# Lower_Board.net
KiCad netlist of a schematic drawn in EAGLE
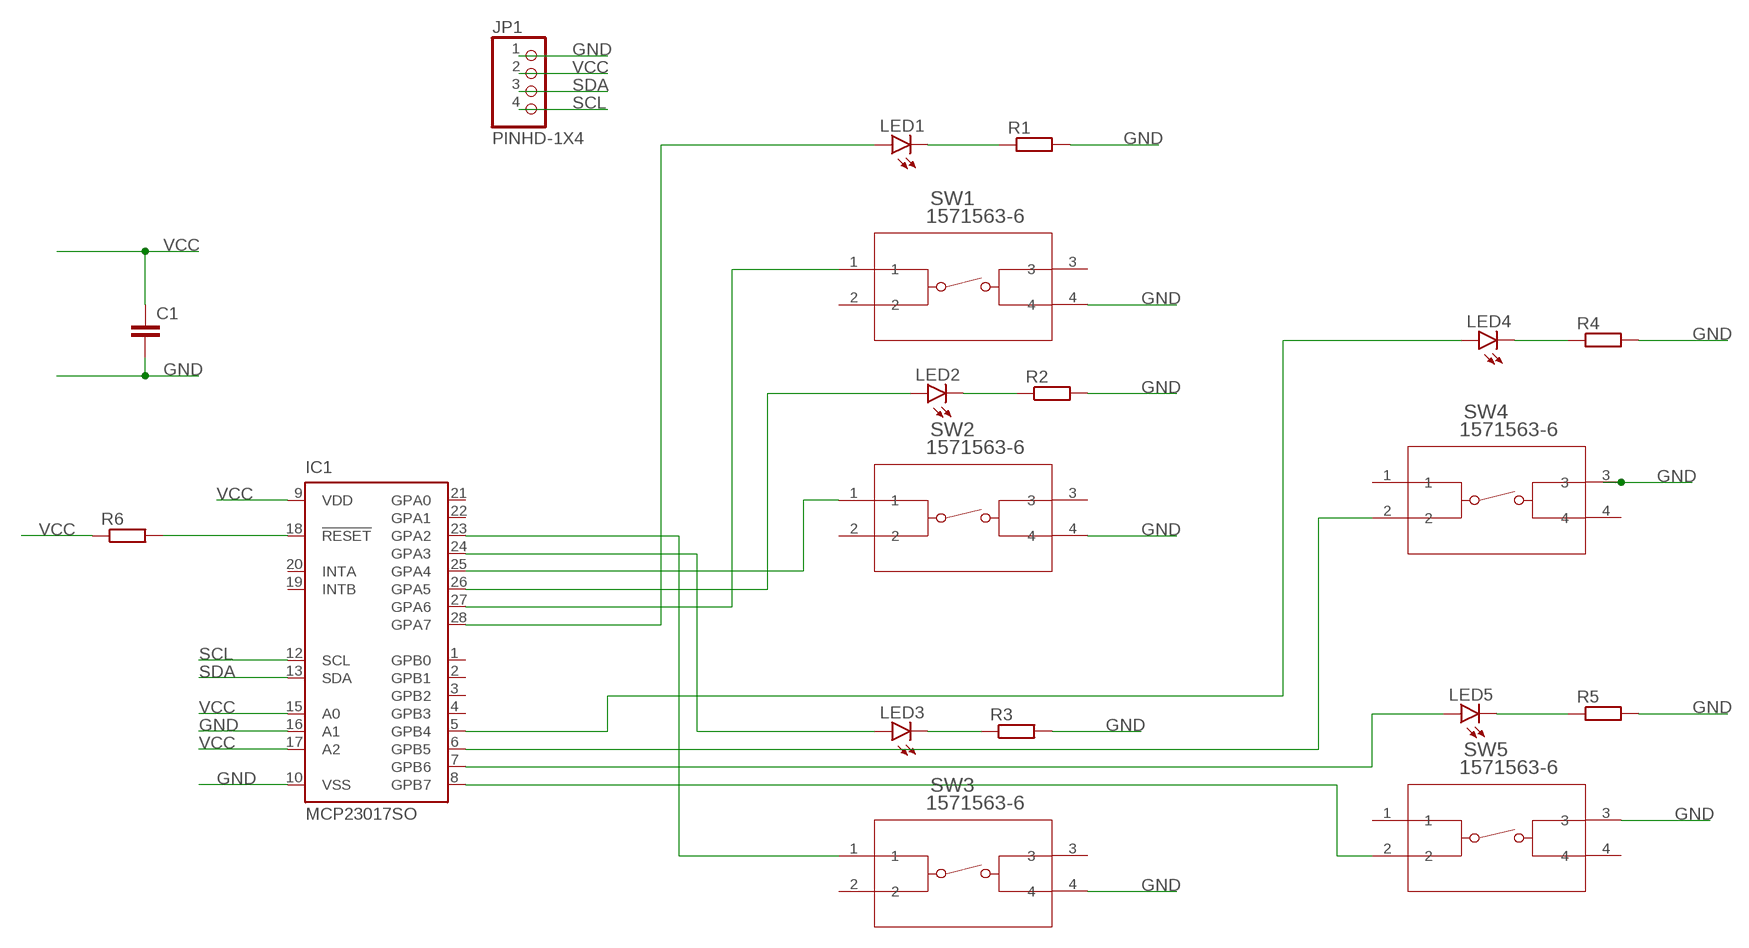
[diagram p0: schematic, sheet 1]

(export (version "E")
  (design (tool "Eeschema 10.0.6"))
  (components
    (comp (ref "C1")
      (value "C-EU025-025X050")
      (footprint "eagle-import:C025-025X050")
      (libsource (lib "eagle-import") (part "C-EU025-025X050"))
    )
    (comp (ref "IC1")
      (value "MCP23017SO")
      (footprint "eagle-import:SO28W")
      (fields (field (name "MF") "MICROCHIP") (field (name "MPN") "MCP23017-E/SO"))
      (libsource (lib "eagle-import") (part "MCP23017SO"))
    )
    (comp (ref "JP1")
      (value "PINHD-1X4")
      (footprint "eagle-import:1X04")
      (libsource (lib "eagle-import") (part "PINHD-1X4"))
    )
    (comp (ref "LED1")
      (value "LEDCHIP-LED0805")
      (footprint "eagle-import:CHIP-LED0805")
      (libsource (lib "eagle-import") (part "LEDCHIP-LED0805"))
    )
    (comp (ref "LED2")
      (value "LEDCHIP-LED0805")
      (footprint "eagle-import:CHIP-LED0805")
      (libsource (lib "eagle-import") (part "LEDCHIP-LED0805"))
    )
    (comp (ref "LED3")
      (value "LEDCHIP-LED0805")
      (footprint "eagle-import:CHIP-LED0805")
      (libsource (lib "eagle-import") (part "LEDCHIP-LED0805"))
    )
    (comp (ref "LED4")
      (value "LEDCHIP-LED0805")
      (footprint "eagle-import:CHIP-LED0805")
      (libsource (lib "eagle-import") (part "LEDCHIP-LED0805"))
    )
    (comp (ref "LED5")
      (value "LEDCHIP-LED0805")
      (footprint "eagle-import:CHIP-LED0805")
      (libsource (lib "eagle-import") (part "LEDCHIP-LED0805"))
    )
    (comp (ref "R1")
      (value "R-EU_R0805")
      (footprint "eagle-import:R0805")
      (libsource (lib "eagle-import") (part "R-EU_R0805"))
    )
    (comp (ref "R2")
      (value "R-EU_R0805")
      (footprint "eagle-import:R0805")
      (libsource (lib "eagle-import") (part "R-EU_R0805"))
    )
    (comp (ref "R3")
      (value "R-EU_R0805")
      (footprint "eagle-import:R0805")
      (libsource (lib "eagle-import") (part "R-EU_R0805"))
    )
    (comp (ref "R4")
      (value "R-EU_R0805")
      (footprint "eagle-import:R0805")
      (libsource (lib "eagle-import") (part "R-EU_R0805"))
    )
    (comp (ref "R5")
      (value "R-EU_R0805")
      (footprint "eagle-import:R0805")
      (libsource (lib "eagle-import") (part "R-EU_R0805"))
    )
    (comp (ref "R6")
      (value "R-EU_R0805")
      (footprint "eagle-import:R0805")
      (libsource (lib "eagle-import") (part "R-EU_R0805"))
    )
    (comp (ref "SW1")
      (value "1571563-6")
      (footprint "eagle-import:SW4_1437565-E")
      (fields (field (name "COPYRIGHT") "Copyright (C) 2016 Accelerated Designs. All rights reserved"))
      (libsource (lib "eagle-import") (part "1571563-6"))
    )
    (comp (ref "SW2")
      (value "1571563-6")
      (footprint "eagle-import:SW4_1437565-E")
      (fields (field (name "COPYRIGHT") "Copyright (C) 2016 Accelerated Designs. All rights reserved"))
      (libsource (lib "eagle-import") (part "1571563-6"))
    )
    (comp (ref "SW3")
      (value "1571563-6")
      (footprint "eagle-import:SW4_1437565-E")
      (fields (field (name "COPYRIGHT") "Copyright (C) 2016 Accelerated Designs. All rights reserved"))
      (libsource (lib "eagle-import") (part "1571563-6"))
    )
    (comp (ref "SW4")
      (value "1571563-6")
      (footprint "eagle-import:SW4_1437565-E")
      (fields (field (name "COPYRIGHT") "Copyright (C) 2016 Accelerated Designs. All rights reserved"))
      (libsource (lib "eagle-import") (part "1571563-6"))
    )
    (comp (ref "SW5")
      (value "1571563-6")
      (footprint "eagle-import:SW4_1437565-E")
      (fields (field (name "COPYRIGHT") "Copyright (C) 2016 Accelerated Designs. All rights reserved"))
      (libsource (lib "eagle-import") (part "1571563-6"))
    )
  )
  (nets
    (net (code "1") (name "/GND") (class "Default")
      (node (ref "C1") (pin "2") (pinfunction "2_2") (pintype "passive"))
      (node (ref "IC1") (pin "10") (pinfunction "VSS_10") (pintype "power_in"))
      (node (ref "IC1") (pin "16") (pinfunction "A1_16") (pintype "input"))
      (node (ref "JP1") (pin "1") (pinfunction "1_1") (pintype "passive"))
      (node (ref "R1") (pin "2") (pinfunction "2_2") (pintype "passive"))
      (node (ref "R2") (pin "2") (pinfunction "2_2") (pintype "passive"))
      (node (ref "R3") (pin "2") (pinfunction "2_2") (pintype "passive"))
      (node (ref "R4") (pin "2") (pinfunction "2_2") (pintype "passive"))
      (node (ref "R5") (pin "2") (pinfunction "2_2") (pintype "passive"))
      (node (ref "SW1") (pin "4") (pinfunction "4_4") (pintype "passive"))
      (node (ref "SW2") (pin "4") (pinfunction "4_4") (pintype "passive"))
      (node (ref "SW3") (pin "4") (pinfunction "4_4") (pintype "passive"))
      (node (ref "SW4") (pin "3") (pinfunction "3_3") (pintype "passive"))
      (node (ref "SW5") (pin "3") (pinfunction "3_3") (pintype "passive"))
    )
    (net (code "2") (name "/SCL") (class "Default")
      (node (ref "IC1") (pin "12") (pinfunction "SCL_12") (pintype "input"))
      (node (ref "JP1") (pin "4") (pinfunction "4_4") (pintype "passive"))
    )
    (net (code "3") (name "/SDA") (class "Default")
      (node (ref "IC1") (pin "13") (pinfunction "SDA_13") (pintype "bidirectional"))
      (node (ref "JP1") (pin "3") (pinfunction "3_3") (pintype "passive"))
    )
    (net (code "4") (name "/VCC") (class "Default")
      (node (ref "C1") (pin "1") (pinfunction "1_1") (pintype "passive"))
      (node (ref "IC1") (pin "15") (pinfunction "A0_15") (pintype "input"))
      (node (ref "IC1") (pin "17") (pinfunction "A2_17") (pintype "input"))
      (node (ref "IC1") (pin "9") (pinfunction "VDD_9") (pintype "power_in"))
      (node (ref "JP1") (pin "2") (pinfunction "2_2") (pintype "passive"))
      (node (ref "R6") (pin "1") (pinfunction "1_1") (pintype "passive"))
    )
    (net (code "5") (name "Net-(IC1-GPA2)") (class "Default")
      (node (ref "IC1") (pin "23") (pinfunction "GPA2_23") (pintype "bidirectional"))
      (node (ref "SW3") (pin "1") (pinfunction "1_1") (pintype "passive"))
    )
    (net (code "6") (name "Net-(IC1-GPA3)") (class "Default")
      (node (ref "IC1") (pin "24") (pinfunction "GPA3_24") (pintype "bidirectional"))
      (node (ref "LED3") (pin "A") (pinfunction "A_A") (pintype "passive"))
    )
    (net (code "7") (name "Net-(IC1-GPA4)") (class "Default")
      (node (ref "IC1") (pin "25") (pinfunction "GPA4_25") (pintype "bidirectional"))
      (node (ref "SW2") (pin "1") (pinfunction "1_1") (pintype "passive"))
    )
    (net (code "8") (name "Net-(IC1-GPA5)") (class "Default")
      (node (ref "IC1") (pin "26") (pinfunction "GPA5_26") (pintype "bidirectional"))
      (node (ref "LED2") (pin "A") (pinfunction "A_A") (pintype "passive"))
    )
    (net (code "9") (name "Net-(IC1-GPA6)") (class "Default")
      (node (ref "IC1") (pin "27") (pinfunction "GPA6_27") (pintype "bidirectional"))
      (node (ref "SW1") (pin "1") (pinfunction "1_1") (pintype "passive"))
    )
    (net (code "10") (name "Net-(IC1-GPA7)") (class "Default")
      (node (ref "IC1") (pin "28") (pinfunction "GPA7_28") (pintype "bidirectional"))
      (node (ref "LED1") (pin "A") (pinfunction "A_A") (pintype "passive"))
    )
    (net (code "11") (name "Net-(IC1-GPB4)") (class "Default")
      (node (ref "IC1") (pin "5") (pinfunction "GPB4_5") (pintype "bidirectional"))
      (node (ref "LED4") (pin "A") (pinfunction "A_A") (pintype "passive"))
    )
    (net (code "12") (name "Net-(IC1-GPB5)") (class "Default")
      (node (ref "IC1") (pin "6") (pinfunction "GPB5_6") (pintype "bidirectional"))
      (node (ref "SW4") (pin "2") (pinfunction "2_2") (pintype "passive"))
    )
    (net (code "13") (name "Net-(IC1-GPB6)") (class "Default")
      (node (ref "IC1") (pin "7") (pinfunction "GPB6_7") (pintype "bidirectional"))
      (node (ref "LED5") (pin "A") (pinfunction "A_A") (pintype "passive"))
    )
    (net (code "14") (name "Net-(IC1-GPB7)") (class "Default")
      (node (ref "IC1") (pin "8") (pinfunction "GPB7_8") (pintype "bidirectional"))
      (node (ref "SW5") (pin "2") (pinfunction "2_2") (pintype "passive"))
    )
    (net (code "15") (name "Net-(IC1-~{RESET})") (class "Default")
      (node (ref "IC1") (pin "18") (pinfunction "~{RESET}_18") (pintype "input"))
      (node (ref "R6") (pin "2") (pinfunction "2_2") (pintype "passive"))
    )
    (net (code "16") (name "Net-(LED1-PadC)") (class "Default")
      (node (ref "LED1") (pin "C") (pinfunction "C_C") (pintype "passive"))
      (node (ref "R1") (pin "1") (pinfunction "1_1") (pintype "passive"))
    )
    (net (code "17") (name "Net-(LED2-PadC)") (class "Default")
      (node (ref "LED2") (pin "C") (pinfunction "C_C") (pintype "passive"))
      (node (ref "R2") (pin "1") (pinfunction "1_1") (pintype "passive"))
    )
    (net (code "18") (name "Net-(LED3-PadC)") (class "Default")
      (node (ref "LED3") (pin "C") (pinfunction "C_C") (pintype "passive"))
      (node (ref "R3") (pin "1") (pinfunction "1_1") (pintype "passive"))
    )
    (net (code "19") (name "Net-(LED4-PadC)") (class "Default")
      (node (ref "LED4") (pin "C") (pinfunction "C_C") (pintype "passive"))
      (node (ref "R4") (pin "1") (pinfunction "1_1") (pintype "passive"))
    )
    (net (code "20") (name "Net-(LED5-PadC)") (class "Default")
      (node (ref "LED5") (pin "C") (pinfunction "C_C") (pintype "passive"))
      (node (ref "R5") (pin "1") (pinfunction "1_1") (pintype "passive"))
    )
    (net (code "21") (name "unconnected-(IC1-GPA0-Pad21)") (class "Default")
      (node (ref "IC1") (pin "21") (pinfunction "GPA0_21") (pintype "bidirectional"))
    )
    (net (code "22") (name "unconnected-(IC1-GPA1-Pad22)") (class "Default")
      (node (ref "IC1") (pin "22") (pinfunction "GPA1_22") (pintype "bidirectional"))
    )
    (net (code "23") (name "unconnected-(IC1-GPB0-Pad1)") (class "Default")
      (node (ref "IC1") (pin "1") (pinfunction "GPB0_1") (pintype "bidirectional"))
    )
    (net (code "24") (name "unconnected-(IC1-GPB1-Pad2)") (class "Default")
      (node (ref "IC1") (pin "2") (pinfunction "GPB1_2") (pintype "bidirectional"))
    )
    (net (code "25") (name "unconnected-(IC1-GPB2-Pad3)") (class "Default")
      (node (ref "IC1") (pin "3") (pinfunction "GPB2_3") (pintype "bidirectional"))
    )
    (net (code "26") (name "unconnected-(IC1-GPB3-Pad4)") (class "Default")
      (node (ref "IC1") (pin "4") (pinfunction "GPB3_4") (pintype "bidirectional"))
    )
    (net (code "27") (name "unconnected-(IC1-INTA-Pad20)") (class "Default")
      (node (ref "IC1") (pin "20") (pinfunction "INTA_20") (pintype "output"))
    )
    (net (code "28") (name "unconnected-(IC1-INTB-Pad19)") (class "Default")
      (node (ref "IC1") (pin "19") (pinfunction "INTB_19") (pintype "output"))
    )
    (net (code "29") (name "unconnected-(SW1-Pad2)") (class "Default")
      (node (ref "SW1") (pin "2") (pinfunction "2_2") (pintype "passive"))
    )
    (net (code "30") (name "unconnected-(SW1-Pad3)") (class "Default")
      (node (ref "SW1") (pin "3") (pinfunction "3_3") (pintype "passive"))
    )
    (net (code "31") (name "unconnected-(SW2-Pad2)") (class "Default")
      (node (ref "SW2") (pin "2") (pinfunction "2_2") (pintype "passive"))
    )
    (net (code "32") (name "unconnected-(SW2-Pad3)") (class "Default")
      (node (ref "SW2") (pin "3") (pinfunction "3_3") (pintype "passive"))
    )
    (net (code "33") (name "unconnected-(SW3-Pad2)") (class "Default")
      (node (ref "SW3") (pin "2") (pinfunction "2_2") (pintype "passive"))
    )
    (net (code "34") (name "unconnected-(SW3-Pad3)") (class "Default")
      (node (ref "SW3") (pin "3") (pinfunction "3_3") (pintype "passive"))
    )
    (net (code "35") (name "unconnected-(SW4-Pad1)") (class "Default")
      (node (ref "SW4") (pin "1") (pinfunction "1_1") (pintype "passive"))
    )
    (net (code "36") (name "unconnected-(SW4-Pad4)") (class "Default")
      (node (ref "SW4") (pin "4") (pinfunction "4_4") (pintype "passive"))
    )
    (net (code "37") (name "unconnected-(SW5-Pad1)") (class "Default")
      (node (ref "SW5") (pin "1") (pinfunction "1_1") (pintype "passive"))
    )
    (net (code "38") (name "unconnected-(SW5-Pad4)") (class "Default")
      (node (ref "SW5") (pin "4") (pinfunction "4_4") (pintype "passive"))
    )
  )
)
